# ring-modulator_-_v_logo.net
KiCad netlist of a schematic drawn in EAGLE
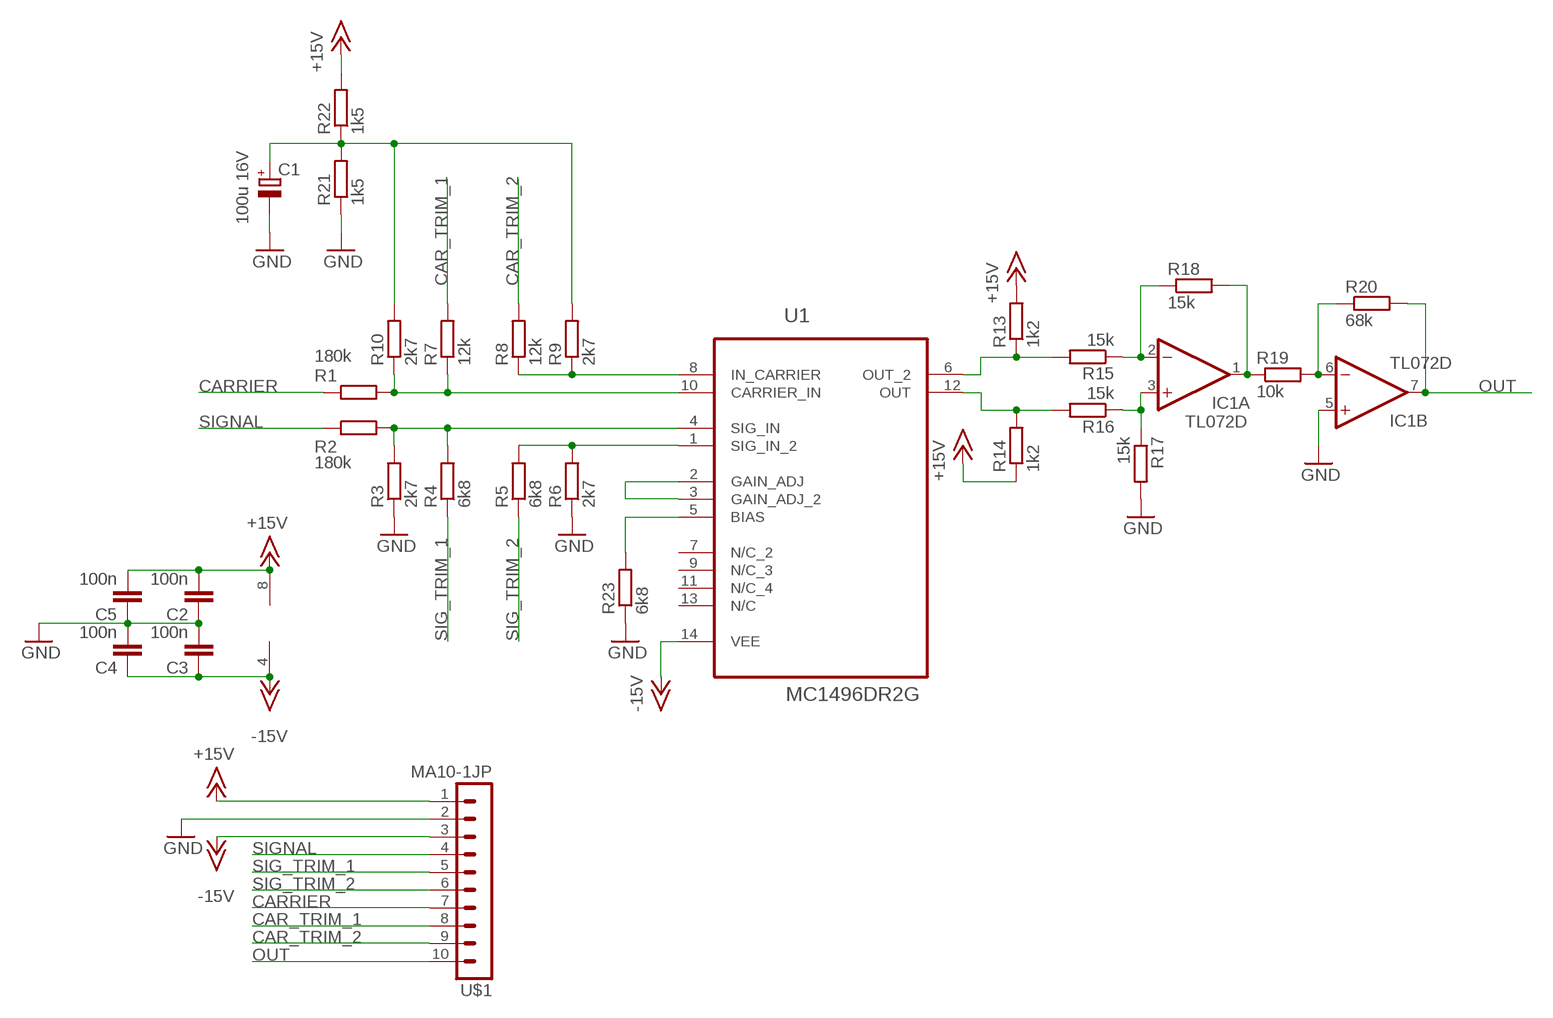
[diagram p0: schematic, sheet 1]

(export (version "E")
  (design (tool "Eeschema 10.0.6"))
  (components
    (comp (ref "C1")
      (value "100u 16V")
      (footprint "eagle-import:E2,5-5")
      (libsource (lib "eagle-import") (part "CPOL-EUE2.5-5"))
    )
    (comp (ref "C2")
      (value "100n")
      (footprint "eagle-import:C0805")
      (libsource (lib "eagle-import") (part "C-EUC0805"))
    )
    (comp (ref "C3")
      (value "100n")
      (footprint "eagle-import:C0805")
      (libsource (lib "eagle-import") (part "C-EUC0805"))
    )
    (comp (ref "C4")
      (value "100n")
      (footprint "eagle-import:C0805")
      (libsource (lib "eagle-import") (part "C-EUC0805"))
    )
    (comp (ref "C5")
      (value "100n")
      (footprint "eagle-import:C0805")
      (libsource (lib "eagle-import") (part "C-EUC0805"))
    )
    (comp (ref "IC1")
      (value "TL072D")
      (footprint "eagle-import:SO08J")
      (libsource (lib "eagle-import") (part "TL072D"))
    )
    (comp (ref "R1")
      (value "180k")
      (footprint "eagle-import:R0805")
      (libsource (lib "eagle-import") (part "R-EU_R0805"))
    )
    (comp (ref "R2")
      (value "180k")
      (footprint "eagle-import:R0805")
      (libsource (lib "eagle-import") (part "R-EU_R0805"))
    )
    (comp (ref "R3")
      (value "2k7")
      (footprint "eagle-import:R0805")
      (libsource (lib "eagle-import") (part "R-EU_R0805"))
    )
    (comp (ref "R4")
      (value "6k8")
      (footprint "eagle-import:R0805")
      (libsource (lib "eagle-import") (part "R-EU_R0805"))
    )
    (comp (ref "R5")
      (value "6k8")
      (footprint "eagle-import:R0805")
      (libsource (lib "eagle-import") (part "R-EU_R0805"))
    )
    (comp (ref "R6")
      (value "2k7")
      (footprint "eagle-import:R0805")
      (libsource (lib "eagle-import") (part "R-EU_R0805"))
    )
    (comp (ref "R7")
      (value "12k")
      (footprint "eagle-import:R0805")
      (libsource (lib "eagle-import") (part "R-EU_R0805"))
    )
    (comp (ref "R8")
      (value "12k")
      (footprint "eagle-import:R0805")
      (libsource (lib "eagle-import") (part "R-EU_R0805"))
    )
    (comp (ref "R9")
      (value "2k7")
      (footprint "eagle-import:R0805")
      (libsource (lib "eagle-import") (part "R-EU_R0805"))
    )
    (comp (ref "R10")
      (value "2k7")
      (footprint "eagle-import:R0805")
      (libsource (lib "eagle-import") (part "R-EU_R0805"))
    )
    (comp (ref "R13")
      (value "1k2")
      (footprint "eagle-import:R0805")
      (libsource (lib "eagle-import") (part "R-EU_R0805"))
    )
    (comp (ref "R14")
      (value "1k2")
      (footprint "eagle-import:R0805")
      (libsource (lib "eagle-import") (part "R-EU_R0805"))
    )
    (comp (ref "R15")
      (value "15k")
      (footprint "eagle-import:R0805")
      (libsource (lib "eagle-import") (part "R-EU_R0805"))
    )
    (comp (ref "R16")
      (value "15k")
      (footprint "eagle-import:R0805")
      (libsource (lib "eagle-import") (part "R-EU_R0805"))
    )
    (comp (ref "R17")
      (value "15k")
      (footprint "eagle-import:R0805")
      (libsource (lib "eagle-import") (part "R-EU_R0805"))
    )
    (comp (ref "R18")
      (value "15k")
      (footprint "eagle-import:R0805")
      (libsource (lib "eagle-import") (part "R-EU_R0805"))
    )
    (comp (ref "R19")
      (value "10k")
      (footprint "eagle-import:R0805")
      (libsource (lib "eagle-import") (part "R-EU_R0805"))
    )
    (comp (ref "R20")
      (value "68k")
      (footprint "eagle-import:R0805")
      (libsource (lib "eagle-import") (part "R-EU_R0805"))
    )
    (comp (ref "R21")
      (value "1k5")
      (footprint "eagle-import:R0805")
      (libsource (lib "eagle-import") (part "R-EU_R0805"))
    )
    (comp (ref "R22")
      (value "1k5")
      (footprint "eagle-import:R0805")
      (libsource (lib "eagle-import") (part "R-EU_R0805"))
    )
    (comp (ref "R23")
      (value "6k8")
      (footprint "eagle-import:R0805")
      (libsource (lib "eagle-import") (part "R-EU_R0805"))
    )
    (comp (ref "U$1")
      (value "MA10-1JP")
      (footprint "eagle-import:SIP-PIN10-1J")
      (libsource (lib "eagle-import") (part "MA10-1JP"))
    )
    (comp (ref "U1")
      (value "MC1496DR2G")
      (footprint "eagle-import:SOIC127P600X175-14N")
      (libsource (lib "eagle-import") (part "MC1496DR2G"))
    )
  )
  (nets
    (net (code "1") (name "+15V") (class "Default")
      (node (ref "C2") (pin "2") (pinfunction "2_2") (pintype "passive"))
      (node (ref "C5") (pin "2") (pinfunction "2_2") (pintype "passive"))
      (node (ref "IC1") (pin "8") (pinfunction "V+_8") (pintype "power_in"))
      (node (ref "R13") (pin "2") (pinfunction "2_2") (pintype "passive"))
      (node (ref "R14") (pin "1") (pinfunction "1_1") (pintype "passive"))
      (node (ref "R22") (pin "2") (pinfunction "2_2") (pintype "passive"))
      (node (ref "U$1") (pin "1") (pinfunction "1_1") (pintype "passive"))
    )
    (net (code "2") (name "-15V") (class "Default")
      (node (ref "C3") (pin "1") (pinfunction "1_1") (pintype "passive"))
      (node (ref "C4") (pin "1") (pinfunction "1_1") (pintype "passive"))
      (node (ref "IC1") (pin "4") (pinfunction "V-_4") (pintype "power_in"))
      (node (ref "U$1") (pin "3") (pinfunction "3_3") (pintype "passive"))
      (node (ref "U1") (pin "14") (pinfunction "VEE_14") (pintype "passive"))
    )
    (net (code "3") (name "/CARRIER") (class "Default")
      (node (ref "R1") (pin "1") (pinfunction "1_1") (pintype "passive"))
      (node (ref "U$1") (pin "7") (pinfunction "7_7") (pintype "passive"))
    )
    (net (code "4") (name "/CAR_TRIM_1") (class "Default")
      (node (ref "R7") (pin "2") (pinfunction "2_2") (pintype "passive"))
      (node (ref "U$1") (pin "8") (pinfunction "8_8") (pintype "passive"))
    )
    (net (code "5") (name "/CAR_TRIM_2") (class "Default")
      (node (ref "R8") (pin "2") (pinfunction "2_2") (pintype "passive"))
      (node (ref "U$1") (pin "9") (pinfunction "9_9") (pintype "passive"))
    )
    (net (code "6") (name "/OUT") (class "Default")
      (node (ref "IC1") (pin "7") (pinfunction "OUT_7") (pintype "output"))
      (node (ref "R20") (pin "2") (pinfunction "2_2") (pintype "passive"))
      (node (ref "U$1") (pin "10") (pinfunction "10_10") (pintype "passive"))
    )
    (net (code "7") (name "/SIGNAL") (class "Default")
      (node (ref "R2") (pin "1") (pinfunction "1_1") (pintype "passive"))
      (node (ref "U$1") (pin "4") (pinfunction "4_4") (pintype "passive"))
    )
    (net (code "8") (name "/SIG_TRIM_1") (class "Default")
      (node (ref "R4") (pin "1") (pinfunction "1_1") (pintype "passive"))
      (node (ref "U$1") (pin "5") (pinfunction "5_5") (pintype "passive"))
    )
    (net (code "9") (name "/SIG_TRIM_2") (class "Default")
      (node (ref "R5") (pin "1") (pinfunction "1_1") (pintype "passive"))
      (node (ref "U$1") (pin "6") (pinfunction "6_6") (pintype "passive"))
    )
    (net (code "10") (name "GND") (class "Default")
      (node (ref "C1") (pin "-") (pinfunction "-_-") (pintype "passive"))
      (node (ref "C2") (pin "1") (pinfunction "1_1") (pintype "passive"))
      (node (ref "C3") (pin "2") (pinfunction "2_2") (pintype "passive"))
      (node (ref "C4") (pin "2") (pinfunction "2_2") (pintype "passive"))
      (node (ref "C5") (pin "1") (pinfunction "1_1") (pintype "passive"))
      (node (ref "IC1") (pin "5") (pinfunction "+IN_5") (pintype "input"))
      (node (ref "R17") (pin "2") (pinfunction "2_2") (pintype "passive"))
      (node (ref "R21") (pin "1") (pinfunction "1_1") (pintype "passive"))
      (node (ref "R23") (pin "1") (pinfunction "1_1") (pintype "passive"))
      (node (ref "R3") (pin "1") (pinfunction "1_1") (pintype "passive"))
      (node (ref "R6") (pin "1") (pinfunction "1_1") (pintype "passive"))
      (node (ref "U$1") (pin "2") (pinfunction "2_2") (pintype "passive"))
    )
    (net (code "11") (name "Net-(C1-Pad+)") (class "Default")
      (node (ref "C1") (pin "+") (pinfunction "+_+") (pintype "passive"))
      (node (ref "R10") (pin "2") (pinfunction "2_2") (pintype "passive"))
      (node (ref "R21") (pin "2") (pinfunction "2_2") (pintype "passive"))
      (node (ref "R22") (pin "1") (pinfunction "1_1") (pintype "passive"))
      (node (ref "R9") (pin "2") (pinfunction "2_2") (pintype "passive"))
    )
    (net (code "12") (name "Net-(IC1A-+IN)") (class "Default")
      (node (ref "IC1") (pin "3") (pinfunction "+IN_3") (pintype "input"))
      (node (ref "R16") (pin "1") (pinfunction "1_1") (pintype "passive"))
      (node (ref "R17") (pin "1") (pinfunction "1_1") (pintype "passive"))
    )
    (net (code "13") (name "Net-(IC1A--IN)") (class "Default")
      (node (ref "IC1") (pin "2") (pinfunction "-IN_2") (pintype "input"))
      (node (ref "R15") (pin "1") (pinfunction "1_1") (pintype "passive"))
      (node (ref "R18") (pin "1") (pinfunction "1_1") (pintype "passive"))
    )
    (net (code "14") (name "Net-(IC1A-OUT)") (class "Default")
      (node (ref "IC1") (pin "1") (pinfunction "OUT_1") (pintype "output"))
      (node (ref "R18") (pin "2") (pinfunction "2_2") (pintype "passive"))
      (node (ref "R19") (pin "1") (pinfunction "1_1") (pintype "passive"))
    )
    (net (code "15") (name "Net-(IC1B--IN)") (class "Default")
      (node (ref "IC1") (pin "6") (pinfunction "-IN_6") (pintype "input"))
      (node (ref "R19") (pin "2") (pinfunction "2_2") (pintype "passive"))
      (node (ref "R20") (pin "1") (pinfunction "1_1") (pintype "passive"))
    )
    (net (code "16") (name "Net-(U1-BIAS)") (class "Default")
      (node (ref "R23") (pin "2") (pinfunction "2_2") (pintype "passive"))
      (node (ref "U1") (pin "5") (pinfunction "BIAS_5") (pintype "input"))
    )
    (net (code "17") (name "Net-(U1-CARRIER_IN)") (class "Default")
      (node (ref "R1") (pin "2") (pinfunction "2_2") (pintype "passive"))
      (node (ref "R10") (pin "1") (pinfunction "1_1") (pintype "passive"))
      (node (ref "R7") (pin "1") (pinfunction "1_1") (pintype "passive"))
      (node (ref "U1") (pin "10") (pinfunction "CARRIER_IN_10") (pintype "power_in"))
    )
    (net (code "18") (name "Net-(U1-GAIN_ADJ)") (class "Default")
      (node (ref "U1") (pin "2") (pinfunction "GAIN_ADJ_2") (pintype "input"))
      (node (ref "U1") (pin "3") (pinfunction "GAIN_ADJ_2_3") (pintype "input"))
    )
    (net (code "19") (name "Net-(U1-IN_CARRIER)") (class "Default")
      (node (ref "R8") (pin "1") (pinfunction "1_1") (pintype "passive"))
      (node (ref "R9") (pin "1") (pinfunction "1_1") (pintype "passive"))
      (node (ref "U1") (pin "8") (pinfunction "IN_CARRIER_8") (pintype "power_in"))
    )
    (net (code "20") (name "Net-(U1-OUT)") (class "Default")
      (node (ref "R14") (pin "2") (pinfunction "2_2") (pintype "passive"))
      (node (ref "R16") (pin "2") (pinfunction "2_2") (pintype "passive"))
      (node (ref "U1") (pin "12") (pinfunction "OUT_12") (pintype "output"))
    )
    (net (code "21") (name "Net-(U1-OUT_2)") (class "Default")
      (node (ref "R13") (pin "1") (pinfunction "1_1") (pintype "passive"))
      (node (ref "R15") (pin "2") (pinfunction "2_2") (pintype "passive"))
      (node (ref "U1") (pin "6") (pinfunction "OUT_2_6") (pintype "output"))
    )
    (net (code "22") (name "Net-(U1-SIG_IN)") (class "Default")
      (node (ref "R2") (pin "2") (pinfunction "2_2") (pintype "passive"))
      (node (ref "R3") (pin "2") (pinfunction "2_2") (pintype "passive"))
      (node (ref "R4") (pin "2") (pinfunction "2_2") (pintype "passive"))
      (node (ref "U1") (pin "4") (pinfunction "SIG_IN_4") (pintype "input"))
    )
    (net (code "23") (name "Net-(U1-SIG_IN_2)") (class "Default")
      (node (ref "R5") (pin "2") (pinfunction "2_2") (pintype "passive"))
      (node (ref "R6") (pin "2") (pinfunction "2_2") (pintype "passive"))
      (node (ref "U1") (pin "1") (pinfunction "SIG_IN_2_1") (pintype "input"))
    )
    (net (code "24") (name "unconnected-(U1-N{slash}C-Pad13)") (class "Default")
      (node (ref "U1") (pin "13") (pinfunction "N/C_13") (pintype "no_connect"))
    )
    (net (code "25") (name "unconnected-(U1-N{slash}C_2-Pad7)") (class "Default")
      (node (ref "U1") (pin "7") (pinfunction "N/C_2_7") (pintype "no_connect"))
    )
    (net (code "26") (name "unconnected-(U1-N{slash}C_3-Pad9)") (class "Default")
      (node (ref "U1") (pin "9") (pinfunction "N/C_3_9") (pintype "no_connect"))
    )
    (net (code "27") (name "unconnected-(U1-N{slash}C_4-Pad11)") (class "Default")
      (node (ref "U1") (pin "11") (pinfunction "N/C_4_11") (pintype "no_connect"))
    )
  )
)
